# Power.net
KiCad netlist of a schematic drawn in Altium Designer
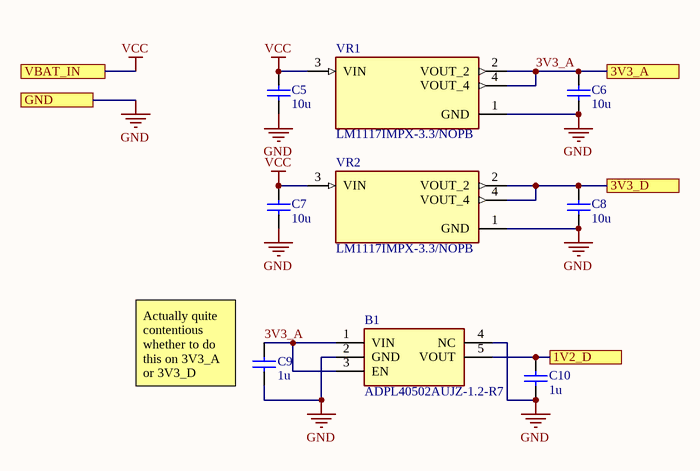
[diagram p0: Power.SchDoc]

(export (version "E")
  (design (tool "Eeschema 10.0.6"))
  (components
    (comp (ref "B1")
      (value "ADPL40502AUJZ-1.2-R7")
      (footprint "SOT95P280X100-5N")
      (description "Low Noise, 200mA, CMOS Linear Regulator")
      (libsource (lib "ADPL40502AUJZ-1.2-R7") (part "ADPL40502AUJZ-1.2-R7"))
    )
    (comp (ref "C5")
      (value "10u")
      (description "Capacitor")
      (libsource (lib "Simulation Generic Components") (part "Capacitor"))
    )
    (comp (ref "C6")
      (value "10u")
      (description "Capacitor")
      (libsource (lib "Simulation Generic Components") (part "Capacitor"))
    )
    (comp (ref "C7")
      (value "10u")
      (description "Capacitor")
      (libsource (lib "Simulation Generic Components") (part "Capacitor"))
    )
    (comp (ref "C8")
      (value "10u")
      (description "Capacitor")
      (libsource (lib "Simulation Generic Components") (part "Capacitor"))
    )
    (comp (ref "C9")
      (value "1u")
      (description "Capacitor")
      (libsource (lib "Simulation Generic Components") (part "Capacitor"))
    )
    (comp (ref "C10")
      (value "1u")
      (description "Capacitor")
      (libsource (lib "Simulation Generic Components") (part "Capacitor"))
    )
    (comp (ref "VR1")
      (value "LM1117IMPX-3.3/NOPB")
      (footprint "VREG_LM1117IMPX-3.3/NOPB")
      (description "800-mA 15-V linear voltage regulator")
      (fields (field (name "MF") "Texas Instruments"))
      (libsource (lib "LM1117IMPX-3.3_NOPB") (part "LM1117IMPX-3.3/NOPB"))
    )
    (comp (ref "VR2")
      (value "LM1117IMPX-3.3/NOPB")
      (footprint "VREG_LM1117IMPX-3.3/NOPB")
      (description "800-mA 15-V linear voltage regulator")
      (fields (field (name "MF") "Texas Instruments"))
      (libsource (lib "LM1117IMPX-3.3_NOPB") (part "LM1117IMPX-3.3/NOPB"))
    )
  )
  (nets
    (net (code "1") (name "/1V2_D") (class "Default")
      (node (ref "B1") (pin "5") (pinfunction "VOUT_5") (pintype "passive"))
      (node (ref "C10") (pin "2") (pinfunction "2_2") (pintype "passive"))
    )
    (net (code "2") (name "/3V3_A") (class "Default")
      (node (ref "B1") (pin "1") (pinfunction "VIN_1") (pintype "passive"))
      (node (ref "B1") (pin "3") (pinfunction "EN_3") (pintype "passive"))
      (node (ref "C6") (pin "2") (pinfunction "2_2") (pintype "passive"))
      (node (ref "C9") (pin "2") (pinfunction "2_2") (pintype "passive"))
      (node (ref "VR1") (pin "2") (pinfunction "VOUT_2_2") (pintype "output"))
      (node (ref "VR1") (pin "4") (pinfunction "VOUT_4_4") (pintype "output"))
    )
    (net (code "3") (name "/3V3_D") (class "Default")
      (node (ref "C8") (pin "2") (pinfunction "2_2") (pintype "passive"))
      (node (ref "VR2") (pin "2") (pinfunction "VOUT_2_2") (pintype "output"))
      (node (ref "VR2") (pin "4") (pinfunction "VOUT_4_4") (pintype "output"))
    )
    (net (code "4") (name "GND") (class "Default")
      (node (ref "B1") (pin "2") (pinfunction "GND_2") (pintype "passive"))
      (node (ref "B1") (pin "4") (pinfunction "NC_4") (pintype "passive"))
      (node (ref "C10") (pin "1") (pinfunction "1_1") (pintype "passive"))
      (node (ref "C5") (pin "1") (pinfunction "1_1") (pintype "passive"))
      (node (ref "C6") (pin "1") (pinfunction "1_1") (pintype "passive"))
      (node (ref "C7") (pin "1") (pinfunction "1_1") (pintype "passive"))
      (node (ref "C8") (pin "1") (pinfunction "1_1") (pintype "passive"))
      (node (ref "C9") (pin "1") (pinfunction "1_1") (pintype "passive"))
      (node (ref "VR1") (pin "1") (pinfunction "GND_1") (pintype "power_in"))
      (node (ref "VR2") (pin "1") (pinfunction "GND_1") (pintype "power_in"))
    )
    (net (code "5") (name "VCC") (class "Default")
      (node (ref "C5") (pin "2") (pinfunction "2_2") (pintype "passive"))
      (node (ref "C7") (pin "2") (pinfunction "2_2") (pintype "passive"))
      (node (ref "VR1") (pin "3") (pinfunction "VIN_3") (pintype "input"))
      (node (ref "VR2") (pin "3") (pinfunction "VIN_3") (pintype "input"))
    )
  )
)
